# CAPSTONE-K_next_Level_Engineering.net
KiCad netlist of a schematic drawn in EasyEDA Pro
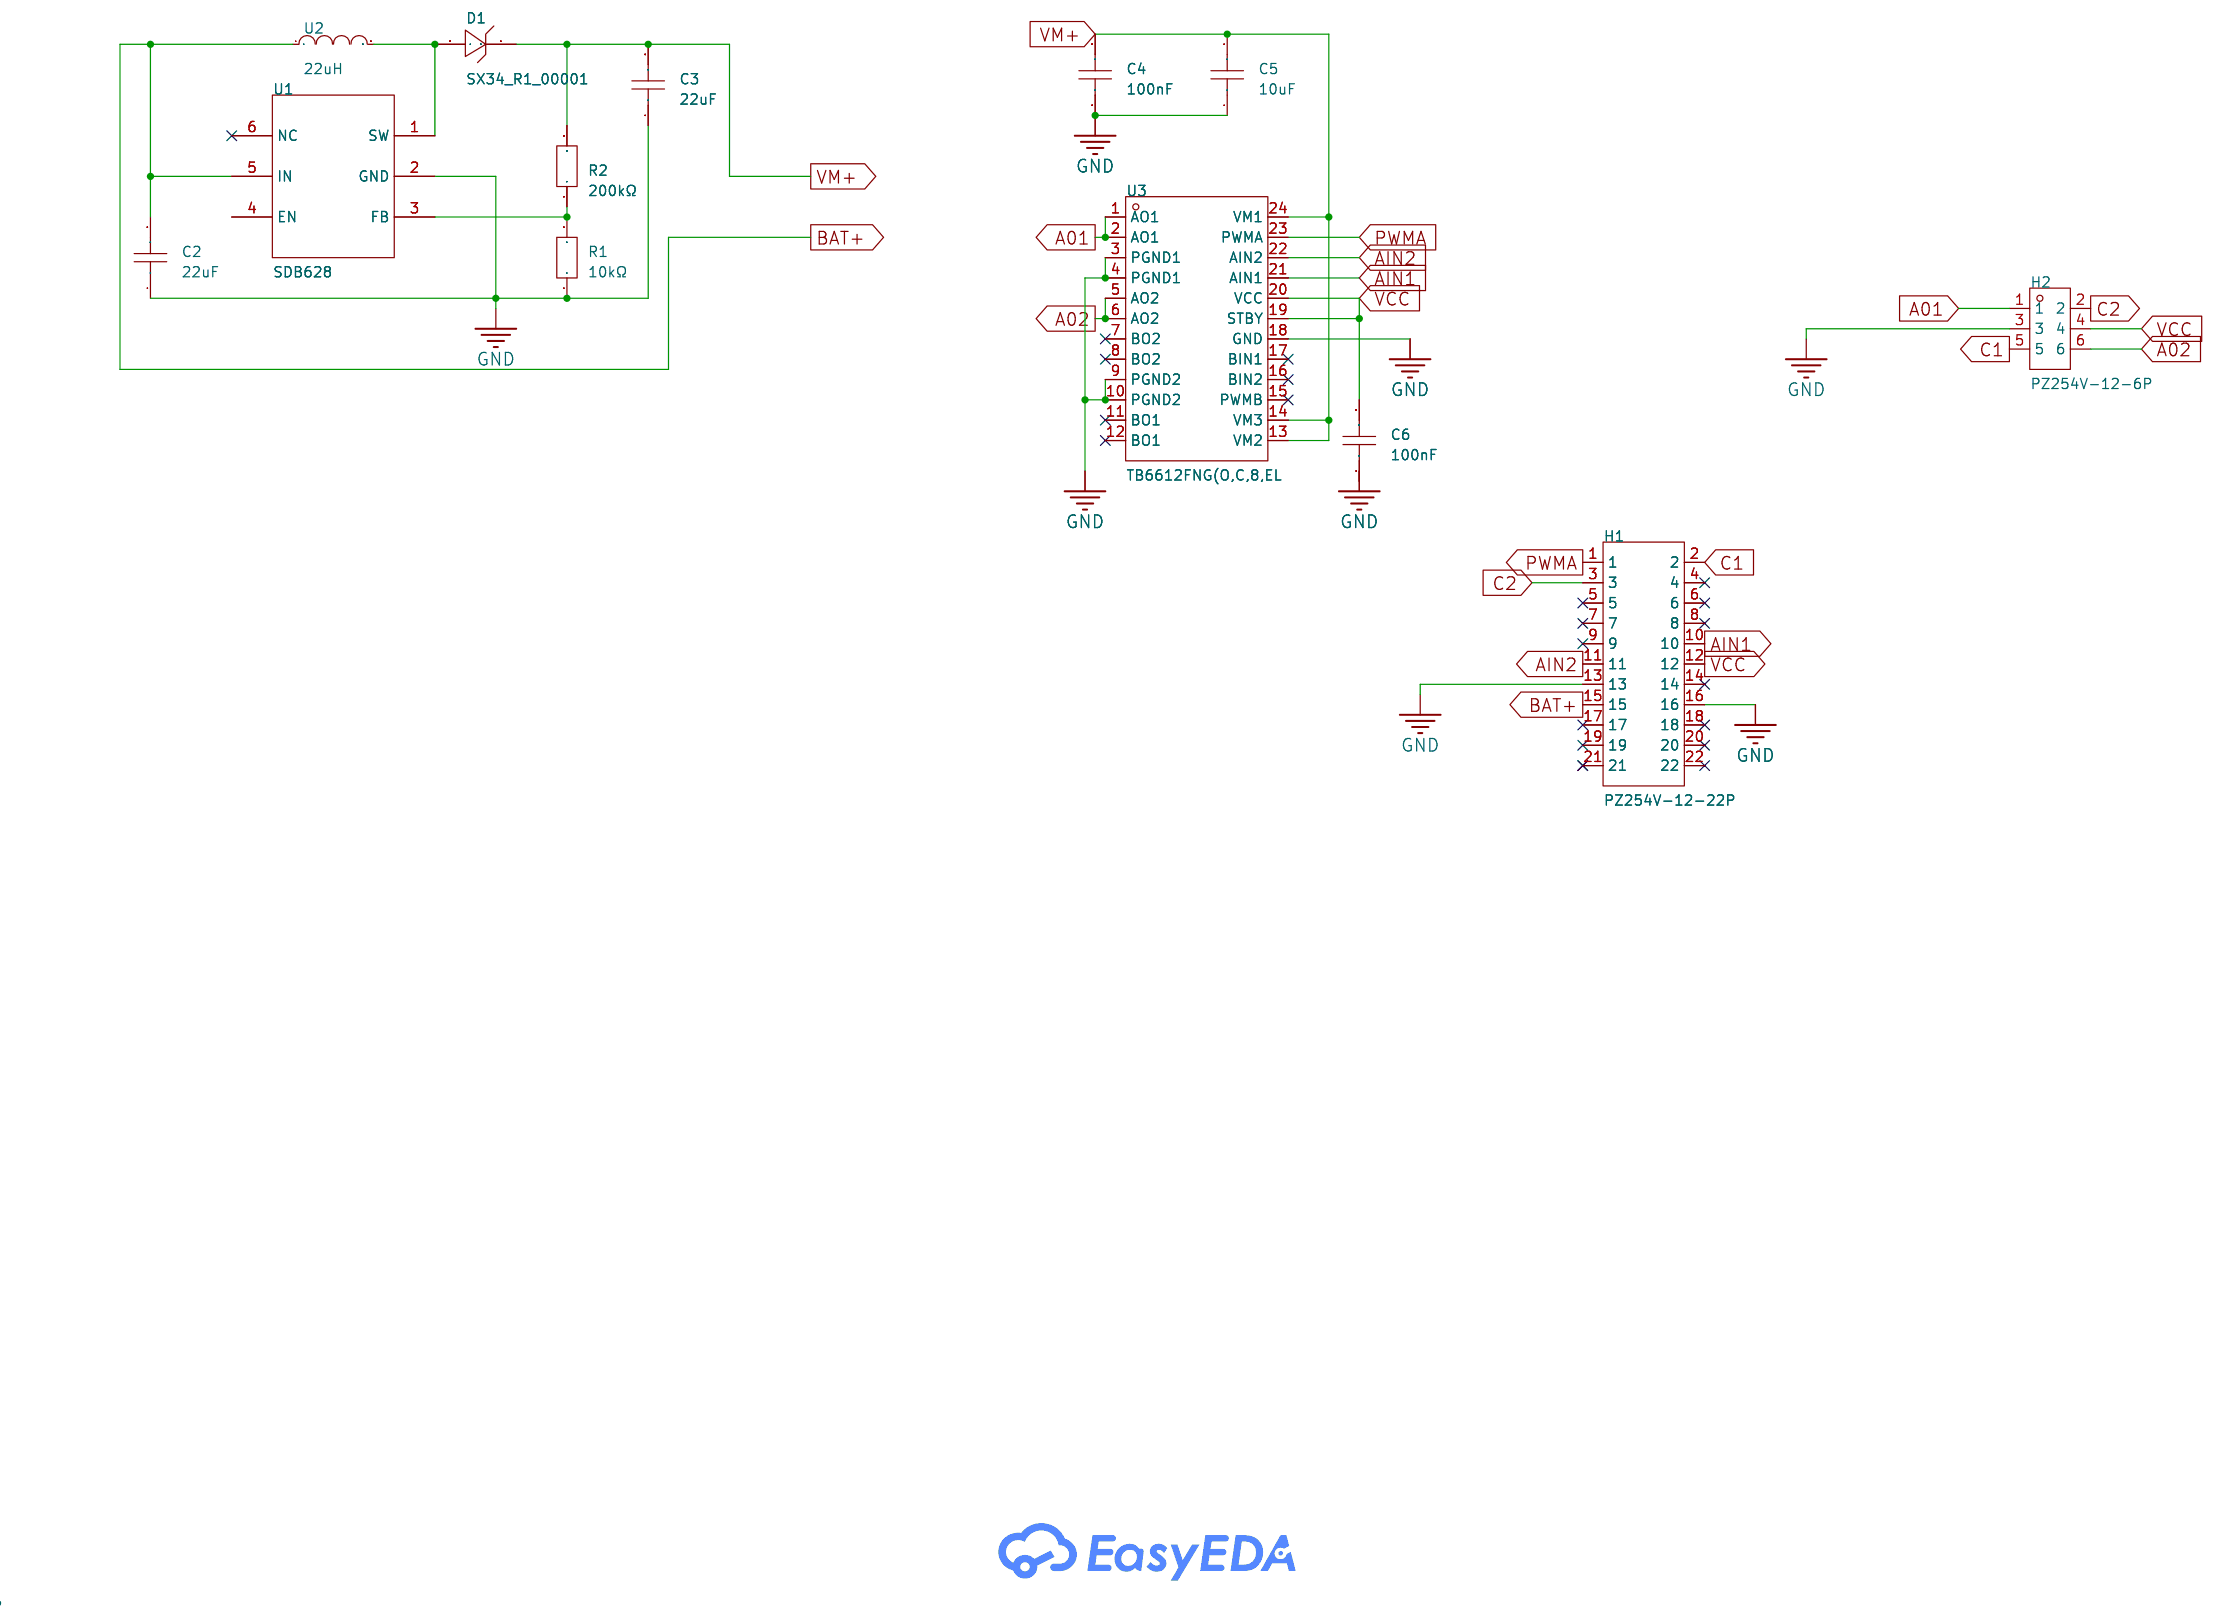
[diagram p0: schematic sheet]

(export (version "E")
  (design (tool "Eeschema 10.0.6"))
  (components
    (comp (ref "C2")
      (value "22uF")
      (footprint "easyedapro:C0603")
      (description "Capacitance:22uF Tolerance:±20% Tolerance:±20% Voltage Rating:6.3V Temperature Coefficient:X5R")
      (fields
        (field (name "Manufacturer Part") "CL10A226MQ8NRNC")
        (field (name "Manufacturer") "SAMSUNG(三星)")
      )
      (libsource (lib "easyedapro") (part "CL10A226MQ8NRNC"))
    )
    (comp (ref "C3")
      (value "22uF")
      (footprint "easyedapro:C0603")
      (description "Capacitance:22uF Tolerance:±20% Tolerance:±20% Voltage Rating:6.3V Temperature Coefficient:X5R")
      (fields
        (field (name "Manufacturer Part") "CL10A226MQ8NRNC")
        (field (name "Manufacturer") "SAMSUNG(三星)")
      )
      (libsource (lib "easyedapro") (part "CL10A226MQ8NRNC"))
    )
    (comp (ref "C4")
      (value "100nF")
      (footprint "easyedapro:C0402")
      (description "Capacitance:100nF Tolerance:±10% Tolerance:±10% Voltage Rating:16V Temperature Coefficient:X7R")
      (fields
        (field (name "Manufacturer Part") "CL05B104KO5NNNC")
        (field (name "Manufacturer") "SAMSUNG(三星)")
      )
      (libsource (lib "easyedapro") (part "CL05B104KO5NNNC"))
    )
    (comp (ref "C5")
      (value "10uF")
      (footprint "easyedapro:C0603")
      (description "Capacitance:10uF Tolerance:±20% Tolerance:±20% Voltage Rating:6.3V Temperature Coefficient:X5R")
      (fields
        (field (name "Manufacturer Part") "CL10A106MQ8NNNC")
        (field (name "Manufacturer") "SAMSUNG(三星)")
      )
      (libsource (lib "easyedapro") (part "CL10A106MQ8NNNC"))
    )
    (comp (ref "C6")
      (value "100nF")
      (footprint "easyedapro:C0402")
      (description "Capacitance:100nF Tolerance:±10% Tolerance:±10% Voltage Rating:16V Temperature Coefficient:X7R")
      (fields
        (field (name "Manufacturer Part") "CL05B104KO5NNNC")
        (field (name "Manufacturer") "SAMSUNG(三星)")
      )
      (libsource (lib "easyedapro") (part "CL05B104KO5NNNC"))
    )
    (comp (ref "D1")
      (value "SX34_R1_00001")
      (footprint "easyedapro:SMA_L4.3-W2.7-LS5.0-RD")
      (fields (field (name "Manufacturer") "PANJIT(强茂)"))
      (libsource (lib "easyedapro") (part "SX34_R1_00001"))
    )
    (comp (ref "H1")
      (value "PZ254V-12-22P")
      (footprint "easyedapro:HDR-TH_22P-P2.54-V-M-R2-C11-S2.54")
      (fields (field (name "Manufacturer") "XFCN(兴飞)"))
      (libsource (lib "easyedapro") (part "PZ254V-12-22P"))
    )
    (comp (ref "H2")
      (value "PZ254V-12-6P")
      (footprint "easyedapro:HDR-TH_6P-P2.54-V-M-R2-C3-S2.54")
      (fields (field (name "Manufacturer") "XFCN(兴飞)"))
      (libsource (lib "easyedapro") (part "PZ254V-12-6P"))
    )
    (comp (ref "R1")
      (value "10kΩ")
      (footprint "easyedapro:R0603")
      (fields (field (name "Manufacturer Part") "FRC0603J103 TS") (field (name "Manufacturer") "FOJAN(富捷)"))
      (libsource (lib "easyedapro") (part "FRC0603J103TS"))
    )
    (comp (ref "R2")
      (value "200kΩ")
      (footprint "easyedapro:R0603")
      (fields (field (name "Manufacturer Part") "FRC0603F2003TS") (field (name "Manufacturer") "FOJAN(富捷)"))
      (libsource (lib "easyedapro") (part "FRC0603F2003TS"))
    )
    (comp (ref "U1")
      (value "SDB628")
      (footprint "easyedapro:SOT-23-6_L2.9-W1.6-P0.95-LS2.8-BL")
      (fields (field (name "Manufacturer") "SHOUDING(首鼎半导体)"))
      (libsource (lib "easyedapro") (part "SDB628"))
    )
    (comp (ref "U2")
      (value "22uH")
      (footprint "easyedapro:IND-SMD_L7.2-W6.6_GPSR07X0")
      (fields (field (name "Manufacturer Part") "CYA0630-22UH") (field (name "Manufacturer") "SHOU HAN(首韩)"))
      (libsource (lib "easyedapro") (part "CYA0630-22UH"))
    )
    (comp (ref "U3")
      (value "TB6612FNG(O,C,8,EL")
      (footprint "easyedapro:SSOP-24_L8.4-W5.8-P0.65-LS7.8-BL")
      (fields (field (name "Manufacturer") "TOSHIBA(东芝)"))
      (libsource (lib "easyedapro") (part "TB6612FNG(O,C,8,EL"))
    )
  )
  (nets
    (net (code "1") (name "A01") (class "Default")
      (node (ref "H2") (pin "1") (pinfunction "1_1") (pintype "unspecified"))
      (node (ref "U3") (pin "1") (pinfunction "AO1_1") (pintype "unspecified"))
      (node (ref "U3") (pin "2") (pinfunction "AO1_2") (pintype "unspecified"))
    )
    (net (code "2") (name "A02") (class "Default")
      (node (ref "H2") (pin "6") (pinfunction "6_6") (pintype "unspecified"))
      (node (ref "U3") (pin "5") (pinfunction "AO2_5") (pintype "unspecified"))
      (node (ref "U3") (pin "6") (pinfunction "AO2_6") (pintype "unspecified"))
    )
    (net (code "3") (name "AIN1") (class "Default")
      (node (ref "H1") (pin "10") (pinfunction "10_10") (pintype "unspecified"))
      (node (ref "U3") (pin "21") (pinfunction "AIN1_21") (pintype "unspecified"))
    )
    (net (code "4") (name "AIN2") (class "Default")
      (node (ref "H1") (pin "11") (pinfunction "11_11") (pintype "unspecified"))
      (node (ref "U3") (pin "22") (pinfunction "AIN2_22") (pintype "unspecified"))
    )
    (net (code "5") (name "BAT+") (class "Default")
      (node (ref "C2") (pin "2") (pinfunction "2_2") (pintype "unspecified"))
      (node (ref "H1") (pin "15") (pinfunction "15_15") (pintype "unspecified"))
      (node (ref "U1") (pin "5") (pinfunction "IN_5") (pintype "unspecified"))
      (node (ref "U2") (pin "1") (pinfunction "1_1") (pintype "unspecified"))
    )
    (net (code "6") (name "C1") (class "Default")
      (node (ref "H1") (pin "2") (pinfunction "2_2") (pintype "unspecified"))
      (node (ref "H2") (pin "5") (pinfunction "5_5") (pintype "unspecified"))
    )
    (net (code "7") (name "C2") (class "Default")
      (node (ref "H1") (pin "3") (pinfunction "3_3") (pintype "unspecified"))
      (node (ref "H2") (pin "2") (pinfunction "2_2") (pintype "unspecified"))
    )
    (net (code "8") (name "GND") (class "Default")
      (node (ref "C2") (pin "1") (pinfunction "1_1") (pintype "unspecified"))
      (node (ref "C3") (pin "1") (pinfunction "1_1") (pintype "unspecified"))
      (node (ref "C4") (pin "1") (pinfunction "1_1") (pintype "unspecified"))
      (node (ref "C5") (pin "1") (pinfunction "1_1") (pintype "unspecified"))
      (node (ref "C6") (pin "1") (pinfunction "1_1") (pintype "unspecified"))
      (node (ref "H1") (pin "13") (pinfunction "13_13") (pintype "unspecified"))
      (node (ref "H1") (pin "16") (pinfunction "16_16") (pintype "unspecified"))
      (node (ref "H2") (pin "3") (pinfunction "3_3") (pintype "unspecified"))
      (node (ref "R1") (pin "1") (pinfunction "1_1") (pintype "unspecified"))
      (node (ref "U1") (pin "2") (pinfunction "GND_2") (pintype "unspecified"))
      (node (ref "U3") (pin "10") (pinfunction "PGND2_10") (pintype "unspecified"))
      (node (ref "U3") (pin "18") (pinfunction "GND_18") (pintype "unspecified"))
      (node (ref "U3") (pin "3") (pinfunction "PGND1_3") (pintype "unspecified"))
      (node (ref "U3") (pin "4") (pinfunction "PGND1_4") (pintype "unspecified"))
      (node (ref "U3") (pin "9") (pinfunction "PGND2_9") (pintype "unspecified"))
    )
    (net (code "9") (name "Net-(D1-A)") (class "Default")
      (node (ref "D1") (pin "2") (pinfunction "A_2") (pintype "unspecified"))
      (node (ref "U1") (pin "1") (pinfunction "SW_1") (pintype "unspecified"))
      (node (ref "U2") (pin "2") (pinfunction "2_2") (pintype "unspecified"))
    )
    (net (code "10") (name "Net-(U1-FB)") (class "Default")
      (node (ref "R1") (pin "2") (pinfunction "2_2") (pintype "unspecified"))
      (node (ref "R2") (pin "1") (pinfunction "1_1") (pintype "unspecified"))
      (node (ref "U1") (pin "3") (pinfunction "FB_3") (pintype "unspecified"))
    )
    (net (code "11") (name "PWMA") (class "Default")
      (node (ref "H1") (pin "1") (pinfunction "1_1") (pintype "unspecified"))
      (node (ref "U3") (pin "23") (pinfunction "PWMA_23") (pintype "unspecified"))
    )
    (net (code "12") (name "VCC") (class "Default")
      (node (ref "C6") (pin "2") (pinfunction "2_2") (pintype "unspecified"))
      (node (ref "H1") (pin "12") (pinfunction "12_12") (pintype "unspecified"))
      (node (ref "H2") (pin "4") (pinfunction "4_4") (pintype "unspecified"))
      (node (ref "U3") (pin "19") (pinfunction "STBY_19") (pintype "unspecified"))
      (node (ref "U3") (pin "20") (pinfunction "VCC_20") (pintype "unspecified"))
    )
    (net (code "13") (name "VM+") (class "Default")
      (node (ref "C3") (pin "2") (pinfunction "2_2") (pintype "unspecified"))
      (node (ref "C4") (pin "2") (pinfunction "2_2") (pintype "unspecified"))
      (node (ref "C5") (pin "2") (pinfunction "2_2") (pintype "unspecified"))
      (node (ref "D1") (pin "1") (pinfunction "C_1") (pintype "unspecified"))
      (node (ref "R2") (pin "2") (pinfunction "2_2") (pintype "unspecified"))
      (node (ref "U3") (pin "13") (pinfunction "VM2_13") (pintype "unspecified"))
      (node (ref "U3") (pin "14") (pinfunction "VM3_14") (pintype "unspecified"))
      (node (ref "U3") (pin "24") (pinfunction "VM1_24") (pintype "unspecified"))
    )
    (net (code "14") (name "unconnected-(H1-Pad4)") (class "Default")
      (node (ref "H1") (pin "4") (pinfunction "4_4") (pintype "unspecified+no_connect"))
    )
    (net (code "15") (name "unconnected-(H1-Pad5)") (class "Default")
      (node (ref "H1") (pin "5") (pinfunction "5_5") (pintype "unspecified+no_connect"))
    )
    (net (code "16") (name "unconnected-(H1-Pad6)") (class "Default")
      (node (ref "H1") (pin "6") (pinfunction "6_6") (pintype "unspecified+no_connect"))
    )
    (net (code "17") (name "unconnected-(H1-Pad7)") (class "Default")
      (node (ref "H1") (pin "7") (pinfunction "7_7") (pintype "unspecified+no_connect"))
    )
    (net (code "18") (name "unconnected-(H1-Pad8)") (class "Default")
      (node (ref "H1") (pin "8") (pinfunction "8_8") (pintype "unspecified+no_connect"))
    )
    (net (code "19") (name "unconnected-(H1-Pad9)") (class "Default")
      (node (ref "H1") (pin "9") (pinfunction "9_9") (pintype "unspecified+no_connect"))
    )
    (net (code "20") (name "unconnected-(H1-Pad14)") (class "Default")
      (node (ref "H1") (pin "14") (pinfunction "14_14") (pintype "unspecified+no_connect"))
    )
    (net (code "21") (name "unconnected-(H1-Pad17)") (class "Default")
      (node (ref "H1") (pin "17") (pinfunction "17_17") (pintype "unspecified+no_connect"))
    )
    (net (code "22") (name "unconnected-(H1-Pad18)") (class "Default")
      (node (ref "H1") (pin "18") (pinfunction "18_18") (pintype "unspecified+no_connect"))
    )
    (net (code "23") (name "unconnected-(H1-Pad19)") (class "Default")
      (node (ref "H1") (pin "19") (pinfunction "19_19") (pintype "unspecified+no_connect"))
    )
    (net (code "24") (name "unconnected-(H1-Pad20)") (class "Default")
      (node (ref "H1") (pin "20") (pinfunction "20_20") (pintype "unspecified+no_connect"))
    )
    (net (code "25") (name "unconnected-(H1-Pad21)") (class "Default")
      (node (ref "H1") (pin "21") (pinfunction "21_21") (pintype "unspecified+no_connect"))
    )
    (net (code "26") (name "unconnected-(H1-Pad22)") (class "Default")
      (node (ref "H1") (pin "22") (pinfunction "22_22") (pintype "unspecified+no_connect"))
    )
    (net (code "27") (name "unconnected-(U1-EN-Pad4)") (class "Default")
      (node (ref "U1") (pin "4") (pinfunction "EN_4") (pintype "unspecified"))
    )
    (net (code "28") (name "unconnected-(U1-NC-Pad6)") (class "Default")
      (node (ref "U1") (pin "6") (pinfunction "NC_6") (pintype "unspecified+no_connect"))
    )
    (net (code "29") (name "unconnected-(U3-BIN1-Pad17)") (class "Default")
      (node (ref "U3") (pin "17") (pinfunction "BIN1_17") (pintype "unspecified+no_connect"))
    )
    (net (code "30") (name "unconnected-(U3-BIN2-Pad16)") (class "Default")
      (node (ref "U3") (pin "16") (pinfunction "BIN2_16") (pintype "unspecified+no_connect"))
    )
    (net (code "31") (name "unconnected-(U3-BO1-Pad11)") (class "Default")
      (node (ref "U3") (pin "11") (pinfunction "BO1_11") (pintype "unspecified+no_connect"))
    )
    (net (code "32") (name "unconnected-(U3-BO1-Pad12)") (class "Default")
      (node (ref "U3") (pin "12") (pinfunction "BO1_12") (pintype "unspecified+no_connect"))
    )
    (net (code "33") (name "unconnected-(U3-BO2-Pad7)") (class "Default")
      (node (ref "U3") (pin "7") (pinfunction "BO2_7") (pintype "unspecified+no_connect"))
    )
    (net (code "34") (name "unconnected-(U3-BO2-Pad8)") (class "Default")
      (node (ref "U3") (pin "8") (pinfunction "BO2_8") (pintype "unspecified+no_connect"))
    )
    (net (code "35") (name "unconnected-(U3-PWMB-Pad15)") (class "Default")
      (node (ref "U3") (pin "15") (pinfunction "PWMB_15") (pintype "unspecified+no_connect"))
    )
  )
)
